# wifi-expansion.net
KiCad netlist of a schematic drawn in EAGLE
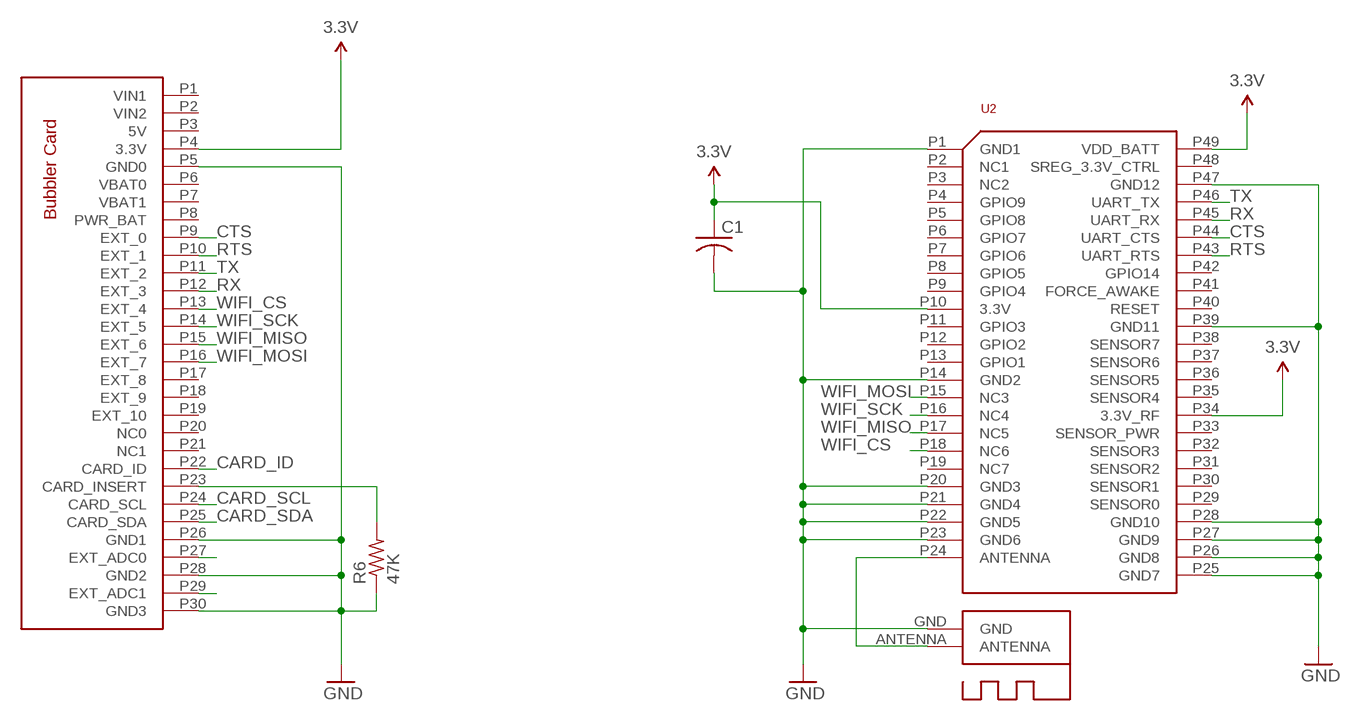
[diagram p0: schematic, sheet 1]
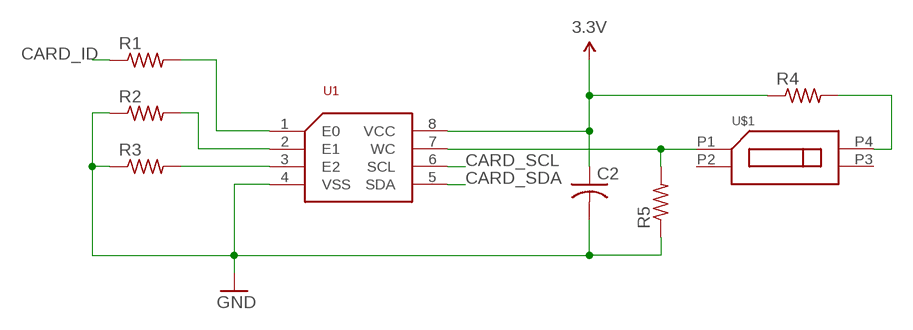
[diagram p1: schematic, sheet 2]

(export (version "E")
  (design (tool "Eeschema 10.0.6"))
  (components
    (comp (ref "C2")
      (value "C-USC0402")
      (footprint "eagle-import:C0402")
      (libsource (lib "eagle-import") (part "C-USC0402"))
    )
    (comp (ref "R1")
      (value "R-US_R0402")
      (footprint "eagle-import:R0402")
      (libsource (lib "eagle-import") (part "R-US_R0402"))
    )
    (comp (ref "R2")
      (value "R-US_R0402")
      (footprint "eagle-import:R0402")
      (libsource (lib "eagle-import") (part "R-US_R0402"))
    )
    (comp (ref "R3")
      (value "R-US_R0402")
      (footprint "eagle-import:R0402")
      (libsource (lib "eagle-import") (part "R-US_R0402"))
    )
    (comp (ref "R4")
      (value "R-US_R0402")
      (footprint "eagle-import:R0402")
      (libsource (lib "eagle-import") (part "R-US_R0402"))
    )
    (comp (ref "R5")
      (value "R-US_R0402")
      (footprint "eagle-import:R0402")
      (libsource (lib "eagle-import") (part "R-US_R0402"))
    )
    (comp (ref "U$1")
      (value "SWITCH-DIP-GDH-02")
      (footprint "eagle-import:SWITCH-DIP-GDH-02")
      (libsource (lib "eagle-import") (part "SWITCH-DIP-GDH-02"))
    )
    (comp (ref "U1")
      (value "EEPROM-ST-M24C64")
      (footprint "eagle-import:TSSOP8")
      (libsource (lib "eagle-import") (part "EEPROM-ST-M24C64"))
    )
    (comp (ref "C1")
      (value "C-USC1206")
      (footprint "eagle-import:C1206")
      (libsource (lib "eagle-import") (part "C-USC1206"))
    )
    (comp (ref "R6")
      (value "47K")
      (footprint "eagle-import:R0402")
      (libsource (lib "eagle-import") (part "R-US_R0402"))
    )
    (comp (ref "U$2")
      (value "BUBBLER_CARD")
      (footprint "eagle-import:CONNECTOR-JAE-TX24-30M")
      (libsource (lib "eagle-import") (part "BUBBLER_CARD"))
    )
    (comp (ref "U$3")
      (value "ANTENNA-RN-171")
      (footprint "eagle-import:RN-171-ANTENNA")
      (libsource (lib "eagle-import") (part "ANTENNA-RN-171"))
    )
    (comp (ref "U2")
      (value "WIFI-RN-171")
      (footprint "eagle-import:WIFI-RN-171")
      (libsource (lib "eagle-import") (part "WIFI-RN-171"))
    )
  )
  (nets
    (net (code "1") (name "3.3V") (class "Default")
      (node (ref "C1") (pin "1") (pinfunction "1_1") (pintype "passive"))
      (node (ref "C2") (pin "1") (pinfunction "1_1") (pintype "passive"))
      (node (ref "R4") (pin "1") (pinfunction "1_1") (pintype "passive"))
      (node (ref "U$2") (pin "P4") (pinfunction "3.3V_P4") (pintype "bidirectional"))
      (node (ref "U1") (pin "8") (pinfunction "VCC_8") (pintype "bidirectional"))
      (node (ref "U2") (pin "P10") (pinfunction "3.3V_P10") (pintype "bidirectional"))
      (node (ref "U2") (pin "P34") (pinfunction "3.3V_RF_P34") (pintype "bidirectional"))
      (node (ref "U2") (pin "P49") (pinfunction "VDD_BATT_P49") (pintype "bidirectional"))
    )
    (net (code "2") (name "CARD_ID") (class "Default")
      (node (ref "R1") (pin "1") (pinfunction "1_1") (pintype "passive"))
      (node (ref "U$2") (pin "P22") (pinfunction "CARD_ID_P22") (pintype "bidirectional"))
    )
    (net (code "3") (name "CARD_SCL") (class "Default")
      (node (ref "U$2") (pin "P24") (pinfunction "CARD_SCL_P24") (pintype "bidirectional"))
      (node (ref "U1") (pin "6") (pinfunction "SCL_6") (pintype "bidirectional"))
    )
    (net (code "4") (name "CARD_SDA") (class "Default")
      (node (ref "U$2") (pin "P25") (pinfunction "CARD_SDA_P25") (pintype "bidirectional"))
      (node (ref "U1") (pin "5") (pinfunction "SDA_5") (pintype "bidirectional"))
    )
    (net (code "5") (name "CTS") (class "Default")
      (node (ref "U$2") (pin "P9") (pinfunction "EXT_0_P9") (pintype "bidirectional"))
      (node (ref "U2") (pin "P44") (pinfunction "UART_CTS_P44") (pintype "bidirectional"))
    )
    (net (code "6") (name "GND") (class "Default")
      (node (ref "C1") (pin "2") (pinfunction "2_2") (pintype "passive"))
      (node (ref "C2") (pin "2") (pinfunction "2_2") (pintype "passive"))
      (node (ref "R2") (pin "1") (pinfunction "1_1") (pintype "passive"))
      (node (ref "R3") (pin "1") (pinfunction "1_1") (pintype "passive"))
      (node (ref "R5") (pin "1") (pinfunction "1_1") (pintype "passive"))
      (node (ref "R6") (pin "1") (pinfunction "1_1") (pintype "passive"))
      (node (ref "U$2") (pin "P26") (pinfunction "GND1_P26") (pintype "bidirectional"))
      (node (ref "U$2") (pin "P28") (pinfunction "GND2_P28") (pintype "bidirectional"))
      (node (ref "U$2") (pin "P30") (pinfunction "GND3_P30") (pintype "bidirectional"))
      (node (ref "U$2") (pin "P5") (pinfunction "GND0_P5") (pintype "bidirectional"))
      (node (ref "U$3") (pin "GND") (pinfunction "GND_GND") (pintype "bidirectional"))
      (node (ref "U1") (pin "4") (pinfunction "VSS_4") (pintype "bidirectional"))
      (node (ref "U2") (pin "P1") (pinfunction "GND1_P1") (pintype "bidirectional"))
      (node (ref "U2") (pin "P14") (pinfunction "GND2_P14") (pintype "bidirectional"))
      (node (ref "U2") (pin "P20") (pinfunction "GND3_P20") (pintype "bidirectional"))
      (node (ref "U2") (pin "P21") (pinfunction "GND4_P21") (pintype "bidirectional"))
      (node (ref "U2") (pin "P22") (pinfunction "GND5_P22") (pintype "bidirectional"))
      (node (ref "U2") (pin "P23") (pinfunction "GND6_P23") (pintype "bidirectional"))
      (node (ref "U2") (pin "P25") (pinfunction "GND7_P25") (pintype "bidirectional"))
      (node (ref "U2") (pin "P26") (pinfunction "GND8_P26") (pintype "bidirectional"))
      (node (ref "U2") (pin "P27") (pinfunction "GND9_P27") (pintype "bidirectional"))
      (node (ref "U2") (pin "P28") (pinfunction "GND10_P28") (pintype "bidirectional"))
      (node (ref "U2") (pin "P39") (pinfunction "GND11_P39") (pintype "bidirectional"))
      (node (ref "U2") (pin "P47") (pinfunction "GND12_P47") (pintype "bidirectional"))
    )
    (net (code "7") (name "Net-(U$1-SW0_0)") (class "Default")
      (node (ref "R5") (pin "2") (pinfunction "2_2") (pintype "passive"))
      (node (ref "U$1") (pin "P1") (pinfunction "SW0_0_P1") (pintype "bidirectional"))
      (node (ref "U1") (pin "7") (pinfunction "WC_7") (pintype "bidirectional"))
    )
    (net (code "8") (name "Net-(U$1-SW0_1)") (class "Default")
      (node (ref "R4") (pin "2") (pinfunction "2_2") (pintype "passive"))
      (node (ref "U$1") (pin "P4") (pinfunction "SW0_1_P4") (pintype "bidirectional"))
    )
    (net (code "9") (name "Net-(U$2-CARD_INSERT)") (class "Default")
      (node (ref "R6") (pin "2") (pinfunction "2_2") (pintype "passive"))
      (node (ref "U$2") (pin "P23") (pinfunction "CARD_INSERT_P23") (pintype "bidirectional"))
    )
    (net (code "10") (name "Net-(U1-E0)") (class "Default")
      (node (ref "R1") (pin "2") (pinfunction "2_2") (pintype "passive"))
      (node (ref "U1") (pin "1") (pinfunction "E0_1") (pintype "bidirectional"))
    )
    (net (code "11") (name "Net-(U1-E1)") (class "Default")
      (node (ref "R2") (pin "2") (pinfunction "2_2") (pintype "passive"))
      (node (ref "U1") (pin "2") (pinfunction "E1_2") (pintype "bidirectional"))
    )
    (net (code "12") (name "Net-(U1-E2)") (class "Default")
      (node (ref "R3") (pin "2") (pinfunction "2_2") (pintype "passive"))
      (node (ref "U1") (pin "3") (pinfunction "E2_3") (pintype "bidirectional"))
    )
    (net (code "13") (name "Net-(U2-ANTENNA)") (class "Default")
      (node (ref "U$3") (pin "ANTENNA") (pinfunction "ANTENNA_ANTENNA") (pintype "bidirectional"))
      (node (ref "U2") (pin "P24") (pinfunction "ANTENNA_P24") (pintype "bidirectional"))
    )
    (net (code "14") (name "RTS") (class "Default")
      (node (ref "U$2") (pin "P10") (pinfunction "EXT_1_P10") (pintype "bidirectional"))
      (node (ref "U2") (pin "P43") (pinfunction "UART_RTS_P43") (pintype "bidirectional"))
    )
    (net (code "15") (name "RX") (class "Default")
      (node (ref "U$2") (pin "P12") (pinfunction "EXT_3_P12") (pintype "bidirectional"))
      (node (ref "U2") (pin "P45") (pinfunction "UART_RX_P45") (pintype "bidirectional"))
    )
    (net (code "16") (name "TX") (class "Default")
      (node (ref "U$2") (pin "P11") (pinfunction "EXT_2_P11") (pintype "bidirectional"))
      (node (ref "U2") (pin "P46") (pinfunction "UART_TX_P46") (pintype "bidirectional"))
    )
    (net (code "17") (name "WIFI_CS") (class "Default")
      (node (ref "U$2") (pin "P13") (pinfunction "EXT_4_P13") (pintype "bidirectional"))
      (node (ref "U2") (pin "P18") (pinfunction "NC6_P18") (pintype "bidirectional"))
    )
    (net (code "18") (name "WIFI_MISO") (class "Default")
      (node (ref "U$2") (pin "P15") (pinfunction "EXT_6_P15") (pintype "bidirectional"))
      (node (ref "U2") (pin "P17") (pinfunction "NC5_P17") (pintype "bidirectional"))
    )
    (net (code "19") (name "WIFI_MOSI") (class "Default")
      (node (ref "U$2") (pin "P16") (pinfunction "EXT_7_P16") (pintype "bidirectional"))
      (node (ref "U2") (pin "P15") (pinfunction "NC3_P15") (pintype "bidirectional"))
    )
    (net (code "20") (name "WIFI_SCK") (class "Default")
      (node (ref "U$2") (pin "P14") (pinfunction "EXT_5_P14") (pintype "bidirectional"))
      (node (ref "U2") (pin "P16") (pinfunction "NC4_P16") (pintype "bidirectional"))
    )
    (net (code "21") (name "unconnected-(U$1-SW1_0-PadP2)") (class "Default")
      (node (ref "U$1") (pin "P2") (pinfunction "SW1_0_P2") (pintype "bidirectional"))
    )
    (net (code "22") (name "unconnected-(U$1-SW1_1-PadP3)") (class "Default")
      (node (ref "U$1") (pin "P3") (pinfunction "SW1_1_P3") (pintype "bidirectional"))
    )
    (net (code "23") (name "unconnected-(U$2-5V-PadP3)") (class "Default")
      (node (ref "U$2") (pin "P3") (pinfunction "5V_P3") (pintype "bidirectional"))
    )
    (net (code "24") (name "unconnected-(U$2-EXT_8-PadP17)") (class "Default")
      (node (ref "U$2") (pin "P17") (pinfunction "EXT_8_P17") (pintype "bidirectional"))
    )
    (net (code "25") (name "unconnected-(U$2-EXT_9-PadP18)") (class "Default")
      (node (ref "U$2") (pin "P18") (pinfunction "EXT_9_P18") (pintype "bidirectional"))
    )
    (net (code "26") (name "unconnected-(U$2-EXT_10-PadP19)") (class "Default")
      (node (ref "U$2") (pin "P19") (pinfunction "EXT_10_P19") (pintype "bidirectional"))
    )
    (net (code "27") (name "unconnected-(U$2-EXT_ADC0-PadP27)") (class "Default")
      (node (ref "U$2") (pin "P27") (pinfunction "EXT_ADC0_P27") (pintype "bidirectional"))
    )
    (net (code "28") (name "unconnected-(U$2-EXT_ADC1-PadP29)") (class "Default")
      (node (ref "U$2") (pin "P29") (pinfunction "EXT_ADC1_P29") (pintype "bidirectional"))
    )
    (net (code "29") (name "unconnected-(U$2-NC0-PadP20)") (class "Default")
      (node (ref "U$2") (pin "P20") (pinfunction "NC0_P20") (pintype "bidirectional"))
    )
    (net (code "30") (name "unconnected-(U$2-NC1-PadP21)") (class "Default")
      (node (ref "U$2") (pin "P21") (pinfunction "NC1_P21") (pintype "bidirectional"))
    )
    (net (code "31") (name "unconnected-(U$2-PWR_BAT-PadP8)") (class "Default")
      (node (ref "U$2") (pin "P8") (pinfunction "PWR_BAT_P8") (pintype "bidirectional"))
    )
    (net (code "32") (name "unconnected-(U$2-VBAT0-PadP6)") (class "Default")
      (node (ref "U$2") (pin "P6") (pinfunction "VBAT0_P6") (pintype "bidirectional"))
    )
    (net (code "33") (name "unconnected-(U$2-VBAT1-PadP7)") (class "Default")
      (node (ref "U$2") (pin "P7") (pinfunction "VBAT1_P7") (pintype "bidirectional"))
    )
    (net (code "34") (name "unconnected-(U$2-VIN1-PadP1)") (class "Default")
      (node (ref "U$2") (pin "P1") (pinfunction "VIN1_P1") (pintype "bidirectional"))
    )
    (net (code "35") (name "unconnected-(U$2-VIN2-PadP2)") (class "Default")
      (node (ref "U$2") (pin "P2") (pinfunction "VIN2_P2") (pintype "bidirectional"))
    )
    (net (code "36") (name "unconnected-(U2-FORCE_AWAKE-PadP41)") (class "Default")
      (node (ref "U2") (pin "P41") (pinfunction "FORCE_AWAKE_P41") (pintype "bidirectional"))
    )
    (net (code "37") (name "unconnected-(U2-GPIO1-PadP13)") (class "Default")
      (node (ref "U2") (pin "P13") (pinfunction "GPIO1_P13") (pintype "bidirectional"))
    )
    (net (code "38") (name "unconnected-(U2-GPIO2-PadP12)") (class "Default")
      (node (ref "U2") (pin "P12") (pinfunction "GPIO2_P12") (pintype "bidirectional"))
    )
    (net (code "39") (name "unconnected-(U2-GPIO3-PadP11)") (class "Default")
      (node (ref "U2") (pin "P11") (pinfunction "GPIO3_P11") (pintype "bidirectional"))
    )
    (net (code "40") (name "unconnected-(U2-GPIO4-PadP9)") (class "Default")
      (node (ref "U2") (pin "P9") (pinfunction "GPIO4_P9") (pintype "bidirectional"))
    )
    (net (code "41") (name "unconnected-(U2-GPIO5-PadP8)") (class "Default")
      (node (ref "U2") (pin "P8") (pinfunction "GPIO5_P8") (pintype "bidirectional"))
    )
    (net (code "42") (name "unconnected-(U2-GPIO6-PadP7)") (class "Default")
      (node (ref "U2") (pin "P7") (pinfunction "GPIO6_P7") (pintype "bidirectional"))
    )
    (net (code "43") (name "unconnected-(U2-GPIO7-PadP6)") (class "Default")
      (node (ref "U2") (pin "P6") (pinfunction "GPIO7_P6") (pintype "bidirectional"))
    )
    (net (code "44") (name "unconnected-(U2-GPIO8-PadP5)") (class "Default")
      (node (ref "U2") (pin "P5") (pinfunction "GPIO8_P5") (pintype "bidirectional"))
    )
    (net (code "45") (name "unconnected-(U2-GPIO9-PadP4)") (class "Default")
      (node (ref "U2") (pin "P4") (pinfunction "GPIO9_P4") (pintype "bidirectional"))
    )
    (net (code "46") (name "unconnected-(U2-GPIO14-PadP42)") (class "Default")
      (node (ref "U2") (pin "P42") (pinfunction "GPIO14_P42") (pintype "bidirectional"))
    )
    (net (code "47") (name "unconnected-(U2-NC1-PadP2)") (class "Default")
      (node (ref "U2") (pin "P2") (pinfunction "NC1_P2") (pintype "bidirectional"))
    )
    (net (code "48") (name "unconnected-(U2-NC2-PadP3)") (class "Default")
      (node (ref "U2") (pin "P3") (pinfunction "NC2_P3") (pintype "bidirectional"))
    )
    (net (code "49") (name "unconnected-(U2-NC7-PadP19)") (class "Default")
      (node (ref "U2") (pin "P19") (pinfunction "NC7_P19") (pintype "bidirectional"))
    )
    (net (code "50") (name "unconnected-(U2-RESET-PadP40)") (class "Default")
      (node (ref "U2") (pin "P40") (pinfunction "RESET_P40") (pintype "bidirectional"))
    )
    (net (code "51") (name "unconnected-(U2-SENSOR0-PadP29)") (class "Default")
      (node (ref "U2") (pin "P29") (pinfunction "SENSOR0_P29") (pintype "bidirectional"))
    )
    (net (code "52") (name "unconnected-(U2-SENSOR1-PadP30)") (class "Default")
      (node (ref "U2") (pin "P30") (pinfunction "SENSOR1_P30") (pintype "bidirectional"))
    )
    (net (code "53") (name "unconnected-(U2-SENSOR2-PadP31)") (class "Default")
      (node (ref "U2") (pin "P31") (pinfunction "SENSOR2_P31") (pintype "bidirectional"))
    )
    (net (code "54") (name "unconnected-(U2-SENSOR3-PadP32)") (class "Default")
      (node (ref "U2") (pin "P32") (pinfunction "SENSOR3_P32") (pintype "bidirectional"))
    )
    (net (code "55") (name "unconnected-(U2-SENSOR4-PadP35)") (class "Default")
      (node (ref "U2") (pin "P35") (pinfunction "SENSOR4_P35") (pintype "bidirectional"))
    )
    (net (code "56") (name "unconnected-(U2-SENSOR5-PadP36)") (class "Default")
      (node (ref "U2") (pin "P36") (pinfunction "SENSOR5_P36") (pintype "bidirectional"))
    )
    (net (code "57") (name "unconnected-(U2-SENSOR6-PadP37)") (class "Default")
      (node (ref "U2") (pin "P37") (pinfunction "SENSOR6_P37") (pintype "bidirectional"))
    )
    (net (code "58") (name "unconnected-(U2-SENSOR7-PadP38)") (class "Default")
      (node (ref "U2") (pin "P38") (pinfunction "SENSOR7_P38") (pintype "bidirectional"))
    )
    (net (code "59") (name "unconnected-(U2-SENSOR_PWR-PadP33)") (class "Default")
      (node (ref "U2") (pin "P33") (pinfunction "SENSOR_PWR_P33") (pintype "bidirectional"))
    )
    (net (code "60") (name "unconnected-(U2-SREG_3.3V_CTRL-PadP48)") (class "Default")
      (node (ref "U2") (pin "P48") (pinfunction "SREG_3.3V_CTRL_P48") (pintype "bidirectional"))
    )
  )
)
